# Sch.net
KiCad netlist of a schematic drawn in Altium Designer
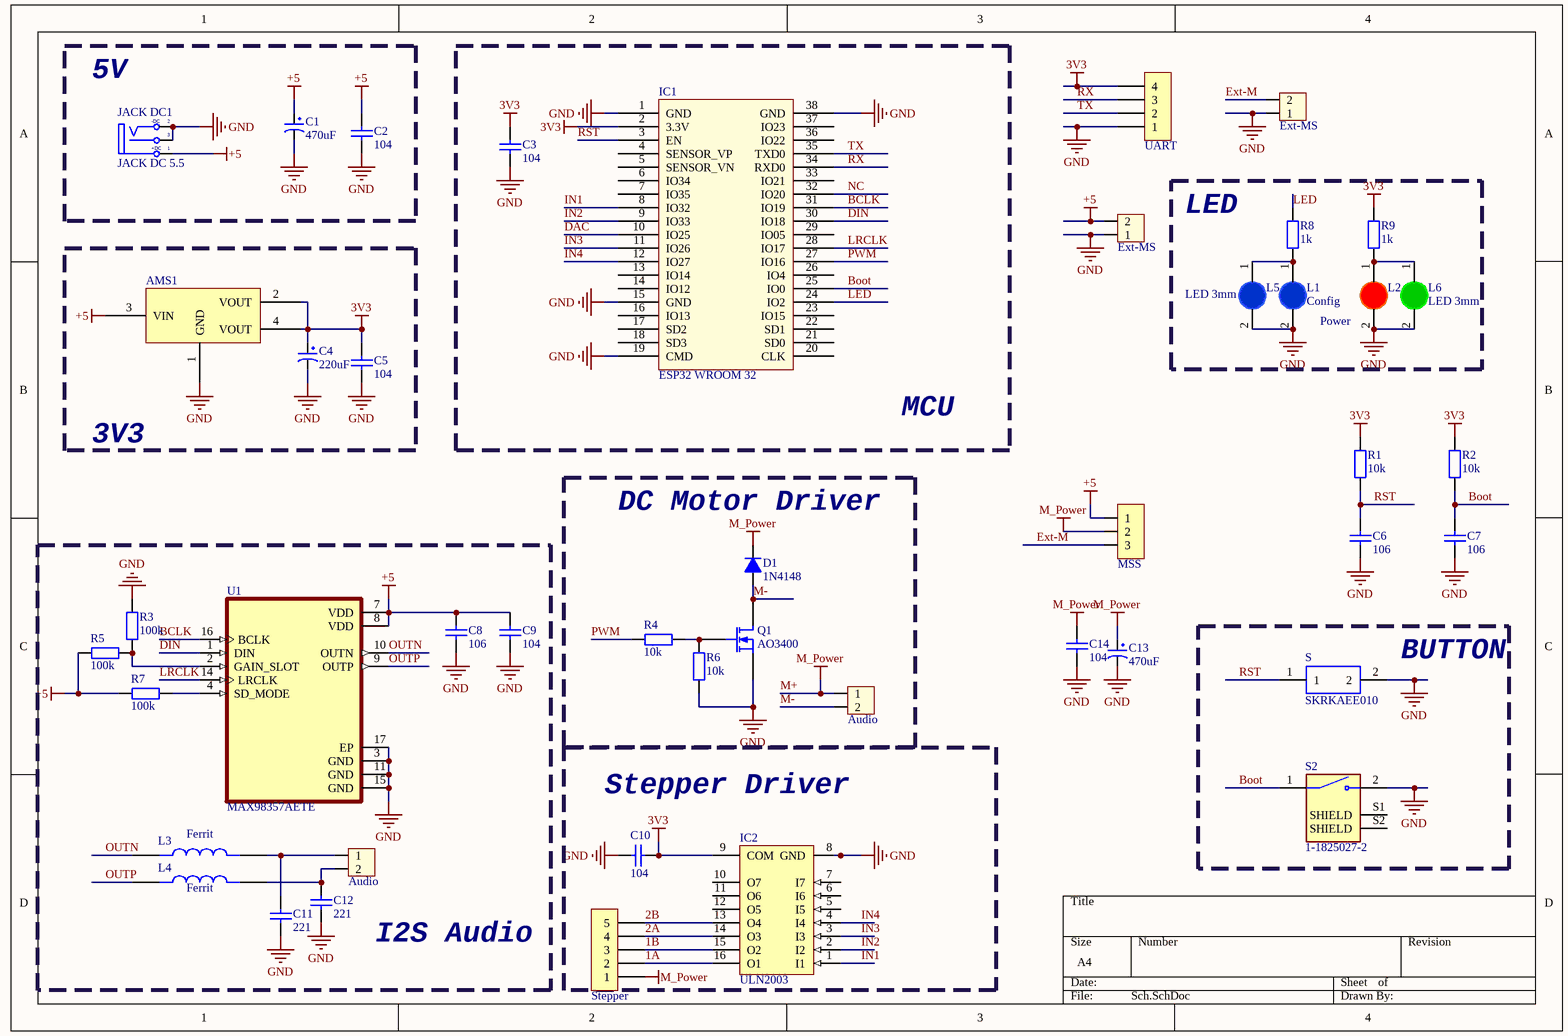
[diagram p0: Sch.SchDoc]

(export (version "E")
  (design (tool "Eeschema 10.0.6"))
  (components
    (comp (ref "AMS1")
      (value "~")
      (footprint "SOT223")
      (description "Dán")
      (libsource (lib "MinhPC_Library") (part "AMS1117 SMD"))
    )
    (comp (ref "C1")
      (value "470uF")
      (footprint "tu hoa 8mm")
      (description "Cắm")
      (libsource (lib "MinhPC_Library") (part "Tu Hoa 470uF 16V 8x11"))
    )
    (comp (ref "C2")
      (value "104")
      (footprint "tu 0805")
      (description "Dán")
      (libsource (lib "MinhPC_Library") (part "Tu 0805 104 50V 10%"))
    )
    (comp (ref "C3")
      (value "104")
      (footprint "tu 0805")
      (description "Dán")
      (libsource (lib "MinhPC_Library") (part "Tu 0805 104 50V 10%"))
    )
    (comp (ref "C4")
      (value "220uF")
      (footprint "tu hoa 5mm")
      (description "Cắm")
      (libsource (lib "MinhPC_Library") (part "Tu Hoa 220uF 10V 6x11"))
    )
    (comp (ref "C5")
      (value "104")
      (footprint "tu 0805")
      (description "Dán")
      (libsource (lib "MinhPC_Library") (part "Tu 0805 104 50V 10%"))
    )
    (comp (ref "C6")
      (value "106")
      (footprint "tu 0805")
      (description "Dán")
      (libsource (lib "MinhPC_Library") (part "Tu 0805 106 16V 10%"))
    )
    (comp (ref "C7")
      (value "106")
      (footprint "tu 0805")
      (description "Dán")
      (libsource (lib "MinhPC_Library") (part "Tu 0805 106 16V 10%"))
    )
    (comp (ref "C8")
      (value "106")
      (footprint "tu 0805")
      (description "Dán")
      (libsource (lib "MinhPC_Library") (part "Tu 0805 106 16V 10%"))
    )
    (comp (ref "C9")
      (value "104")
      (footprint "tu 0805")
      (description "Dán")
      (libsource (lib "MinhPC_Library") (part "Tu 0805 104 50V 10%"))
    )
    (comp (ref "C10")
      (value "104")
      (footprint "tu 0805")
      (description "Dán")
      (libsource (lib "MinhPC_Library") (part "Tu 0805 104 50V 10%"))
    )
    (comp (ref "C11")
      (value "221")
      (footprint "tu 0805")
      (description "Dán")
      (libsource (lib "MinhPC_Library") (part "Tu 0805 224 50V 10%"))
    )
    (comp (ref "C12")
      (value "221")
      (footprint "tu 0805")
      (description "Dán")
      (libsource (lib "MinhPC_Library") (part "Tu 0805 224 50V 10%"))
    )
    (comp (ref "C13")
      (value "470uF")
      (footprint "tu hoa 8mm")
      (description "Cắm")
      (libsource (lib "MinhPC_Library") (part "Tu Hoa 470uF 16V 8x11"))
    )
    (comp (ref "C14")
      (value "104")
      (footprint "tu 0805")
      (description "Dán")
      (libsource (lib "MinhPC_Library") (part "Tu 0805 104 50V 10%"))
    )
    (comp (ref "D1")
      (value "1N4148")
      (footprint "DIODE SOD323F")
      (description "SMD")
      (libsource (lib "MinhPC_Library") (part "1N4148"))
    )
    (comp (ref "H1")
      (value "UART")
      (footprint "XH2.54M-4")
      (description "Cắm")
      (libsource (lib "MinhPC_Library") (part "Header 4P 2.54 Duc Thang"))
    )
    (comp (ref "H2")
      (value "Audio")
      (footprint "XH2.54M-2")
      (description "Cắm")
      (libsource (lib "MinhPC_Library") (part "Header 2P 2.54 Duc Thang"))
    )
    (comp (ref "H3")
      (value "Audio")
      (footprint "XH2.54M-2")
      (description "Cắm")
      (libsource (lib "MinhPC_Library") (part "Header 2P 2.54 Duc Thang"))
    )
    (comp (ref "H4")
      (value "Stepper")
      (footprint "XH2.54M-5")
      (description "Cắm")
      (libsource (lib "MinhPC_Library") (part "Header 5P 2.54 Duc Thang"))
    )
    (comp (ref "H5")
      (value "Ext-MS")
      (footprint "XH2.54M-2")
      (description "Cắm")
      (libsource (lib "") (part "Header 2P 2.54 Duc Thang_1"))
    )
    (comp (ref "H6")
      (value "Ext-MS")
      (footprint "XH2.54M-2")
      (description "Cắm")
      (libsource (lib "") (part "Header 2P 2.54 Duc Thang_1"))
    )
    (comp (ref "IC1")
      (value "ESP32 WROOM 32")
      (footprint "ESP32-WROOM-32D")
      (libsource (lib "MinhPC_Library") (part "ESP32 WROOM 32"))
    )
    (comp (ref "IC2")
      (value "ULN2003")
      (footprint "SOP 16")
      (description "Dán")
      (libsource (lib "MinhPC_Library") (part "ULN2003A SMD"))
    )
    (comp (ref "JACK DC1")
      (value "JACK DC 5.5")
      (footprint "JACK DC 5.5")
      (libsource (lib "MinhPC_Library") (part "JACK DC 5.5"))
    )
    (comp (ref "JP1")
      (value "MSS")
      (footprint "JP 1x3 DT")
      (description "Cắm")
      (libsource (lib "MinhPC_Library") (part "JP 1x3 2.54 Duc Thang"))
    )
    (comp (ref "L1")
      (value "Config")
      (footprint "LED-0805-Blue")
      (description "Dán")
      (libsource (lib "MinhPC_Library") (part "LED 0805 Xanh Duong"))
    )
    (comp (ref "L2")
      (value "Power")
      (footprint "LED-0805-Red")
      (description "Dán")
      (libsource (lib "MinhPC_Library") (part "LED 0805 Do"))
    )
    (comp (ref "L3")
      (value "Ferrit")
      (footprint "INDC2012X105N")
      (description "IND 1uH 0.05A 400mâ„¦")
      (fields (field (name "MP") "AIML-0805-1R0K-T") (field (name "MF") "Abracon"))
      (libsource (lib "AIML-0805-1R0K-T") (part "AIML-0805-1R0K-T"))
    )
    (comp (ref "L4")
      (value "Ferrit")
      (footprint "INDC2012X105N")
      (description "IND 1uH 0.05A 400mâ„¦")
      (fields (field (name "MP") "AIML-0805-1R0K-T") (field (name "MF") "Abracon"))
      (libsource (lib "AIML-0805-1R0K-T") (part "AIML-0805-1R0K-T"))
    )
    (comp (ref "L5")
      (value "LED 3mm")
      (footprint "LED-3MM-BLUE")
      (description "Cắm")
      (libsource (lib "MinhPC_Library") (part "LED 3mm Xanh Duong"))
    )
    (comp (ref "L6")
      (value "LED 3mm")
      (footprint "LED-3MM-GREEN")
      (description "Cắm")
      (libsource (lib "MinhPC_Library") (part "LED 3mm Xanh La"))
    )
    (comp (ref "Q1")
      (value "AO3400")
      (footprint "SOT23")
      (description "N-Channel MOSFET")
      (fields (field (name "PUBLISHER") "Altium Limited"))
      (libsource (lib "MinhPC_Library") (part "Si2302DS"))
    )
    (comp (ref "R1")
      (value "10k")
      (footprint "tro smd 0805")
      (description "Dán")
      (libsource (lib "MinhPC_Library") (part "Tro 0805 5% 10k"))
    )
    (comp (ref "R2")
      (value "10k")
      (footprint "tro smd 0805")
      (description "Dán")
      (libsource (lib "MinhPC_Library") (part "Tro 0805 5% 10k"))
    )
    (comp (ref "R3")
      (value "100k")
      (footprint "tro smd 0805")
      (description "Dán")
      (libsource (lib "MinhPC_Library") (part "Tro 0805 5% 10k"))
    )
    (comp (ref "R4")
      (value "10k")
      (footprint "tro smd 0805")
      (description "Dán")
      (libsource (lib "MinhPC_Library") (part "Tro 0805 5% 10k"))
    )
    (comp (ref "R5")
      (value "100k")
      (footprint "tro smd 0805")
      (description "Dán")
      (libsource (lib "MinhPC_Library") (part "Tro 0805 5% 10k"))
    )
    (comp (ref "R6")
      (value "10k")
      (footprint "tro smd 0805")
      (description "Dán")
      (libsource (lib "MinhPC_Library") (part "Tro 0805 5% 10k"))
    )
    (comp (ref "R7")
      (value "100k")
      (footprint "tro smd 0805")
      (description "Dán")
      (libsource (lib "MinhPC_Library") (part "Tro 0805 5% 10k"))
    )
    (comp (ref "R8")
      (value "1k")
      (footprint "tro smd 0805")
      (description "Dán")
      (libsource (lib "MinhPC_Library") (part "Tro 0805 5% 10k"))
    )
    (comp (ref "R9")
      (value "1k")
      (footprint "tro smd 0805")
      (description "Dán")
      (libsource (lib "MinhPC_Library") (part "Tro 0805 5% 10k"))
    )
    (comp (ref "S")
      (value "SKRKAEE010")
      (footprint "SKRK")
      (description "Switch Tactile N.O. SPST Round Button Gull Wing 0.05A 12VDC 1.57N SMD T/R")
      (fields (field (name "MF") "ALPS"))
      (libsource (lib "SKRKAEE010") (part "SKRKAEE010"))
    )
    (comp (ref "S2")
      (value "1-1825027-2")
      (footprint "SW_1-1825027-2")
      (description "Tactile Switch SPST-NO Side Actuated Through Hole, Right Angle")
      (fields (field (name "MF") "TE Connectivity"))
      (libsource (lib "1-1825027-2") (part "1-1825027-2"))
    )
    (comp (ref "U1")
      (value "MAX98357AETE")
      (footprint "QFN50P300X300X80-17N")
      (description "Audio Amp Speaker 1-CH Mono 3.2W Class-D 16-Pin TQFN EP T/R")
      (fields (field (name "MF") "Maxim Integrated"))
      (libsource (lib "MAX98357AETE") (part "MAX98357AETE"))
    )
  )
  (nets
    (net (code "1") (name "+5") (class "Default")
      (node (ref "AMS1") (pin "3") (pinfunction "VIN_3") (pintype "passive"))
      (node (ref "C1") (pin "1") (pinfunction "1_1") (pintype "passive"))
      (node (ref "C2") (pin "1") (pinfunction "1_1") (pintype "passive"))
      (node (ref "C8") (pin "1") (pinfunction "1_1") (pintype "passive"))
      (node (ref "C9") (pin "1") (pinfunction "1_1") (pintype "passive"))
      (node (ref "H6") (pin "2") (pinfunction "2_2") (pintype "passive"))
      (node (ref "JACK DC1") (pin "1") (pinfunction "T_1") (pintype "passive"))
      (node (ref "JP1") (pin "1") (pinfunction "1_1") (pintype "passive"))
      (node (ref "R5") (pin "2") (pinfunction "2_2") (pintype "passive"))
      (node (ref "R7") (pin "2") (pinfunction "2_2") (pintype "passive"))
      (node (ref "U1") (pin "7") (pinfunction "VDD_7") (pintype "power_in"))
      (node (ref "U1") (pin "8") (pinfunction "VDD_8") (pintype "power_in"))
    )
    (net (code "2") (name "/1A") (class "Default")
      (node (ref "H4") (pin "2") (pinfunction "2_2") (pintype "passive"))
      (node (ref "IC2") (pin "16") (pinfunction "O1_16") (pintype "open_collector"))
    )
    (net (code "3") (name "/1B") (class "Default")
      (node (ref "H4") (pin "3") (pinfunction "3_3") (pintype "passive"))
      (node (ref "IC2") (pin "15") (pinfunction "O2_15") (pintype "open_collector"))
    )
    (net (code "4") (name "/2A") (class "Default")
      (node (ref "H4") (pin "4") (pinfunction "4_4") (pintype "passive"))
      (node (ref "IC2") (pin "14") (pinfunction "O3_14") (pintype "open_collector"))
    )
    (net (code "5") (name "/2B") (class "Default")
      (node (ref "H4") (pin "5") (pinfunction "5_5") (pintype "passive"))
      (node (ref "IC2") (pin "13") (pinfunction "O4_13") (pintype "open_collector"))
    )
    (net (code "6") (name "/BCLK") (class "Default")
      (node (ref "IC1") (pin "31") (pinfunction "IO19_31") (pintype "passive"))
      (node (ref "U1") (pin "16") (pinfunction "BCLK_16") (pintype "input"))
    )
    (net (code "7") (name "/Boot") (class "Default")
      (node (ref "C7") (pin "1") (pinfunction "1_1") (pintype "passive"))
      (node (ref "IC1") (pin "25") (pinfunction "IO0_25") (pintype "passive"))
      (node (ref "R2") (pin "1") (pinfunction "1_1") (pintype "passive"))
      (node (ref "S2") (pin "1") (pinfunction "1_1") (pintype "passive"))
    )
    (net (code "8") (name "/DAC") (class "Default")
      (node (ref "IC1") (pin "10") (pinfunction "IO25_10") (pintype "passive"))
    )
    (net (code "9") (name "/DIN") (class "Default")
      (node (ref "IC1") (pin "30") (pinfunction "IO18_30") (pintype "passive"))
      (node (ref "U1") (pin "1") (pinfunction "DIN_1") (pintype "input"))
    )
    (net (code "10") (name "/Ext-M") (class "Default")
      (node (ref "H5") (pin "2") (pinfunction "2_2") (pintype "passive"))
      (node (ref "JP1") (pin "3") (pinfunction "3_3") (pintype "passive"))
    )
    (net (code "11") (name "/IN1") (class "Default")
      (node (ref "IC1") (pin "8") (pinfunction "IO32_8") (pintype "passive"))
      (node (ref "IC2") (pin "1") (pinfunction "I1_1") (pintype "input"))
    )
    (net (code "12") (name "/IN2") (class "Default")
      (node (ref "IC1") (pin "9") (pinfunction "IO33_9") (pintype "passive"))
      (node (ref "IC2") (pin "2") (pinfunction "I2_2") (pintype "input"))
    )
    (net (code "13") (name "/IN3") (class "Default")
      (node (ref "IC1") (pin "11") (pinfunction "IO26_11") (pintype "passive"))
      (node (ref "IC2") (pin "3") (pinfunction "I3_3") (pintype "input"))
    )
    (net (code "14") (name "/IN4") (class "Default")
      (node (ref "IC1") (pin "12") (pinfunction "IO27_12") (pintype "passive"))
      (node (ref "IC2") (pin "4") (pinfunction "I4_4") (pintype "input"))
    )
    (net (code "15") (name "/LED") (class "Default")
      (node (ref "IC1") (pin "24") (pinfunction "IO2_24") (pintype "passive"))
      (node (ref "R8") (pin "2") (pinfunction "2_2") (pintype "passive"))
    )
    (net (code "16") (name "/LRCLK") (class "Default")
      (node (ref "IC1") (pin "28") (pinfunction "IO17_28") (pintype "passive"))
      (node (ref "U1") (pin "14") (pinfunction "LRCLK_14") (pintype "input"))
    )
    (net (code "17") (name "/M-") (class "Default")
      (node (ref "D1") (pin "1") (pinfunction "A_1") (pintype "passive"))
      (node (ref "H2") (pin "2") (pinfunction "2_2") (pintype "passive"))
      (node (ref "Q1") (pin "3") (pinfunction "D_3") (pintype "passive"))
    )
    (net (code "18") (name "/NC") (class "Default")
      (node (ref "IC1") (pin "32") (pinfunction "IO20_32") (pintype "passive"))
    )
    (net (code "19") (name "/OUTN") (class "Default")
      (node (ref "L3") (pin "1") (pinfunction "1_1") (pintype "passive"))
      (node (ref "U1") (pin "10") (pinfunction "OUTN_10") (pintype "output"))
    )
    (net (code "20") (name "/OUTP") (class "Default")
      (node (ref "L4") (pin "1") (pinfunction "1_1") (pintype "passive"))
      (node (ref "U1") (pin "9") (pinfunction "OUTP_9") (pintype "output"))
    )
    (net (code "21") (name "/PWM") (class "Default")
      (node (ref "IC1") (pin "27") (pinfunction "IO16_27") (pintype "passive"))
      (node (ref "R4") (pin "2") (pinfunction "2_2") (pintype "passive"))
    )
    (net (code "22") (name "/RST") (class "Default")
      (node (ref "C6") (pin "1") (pinfunction "1_1") (pintype "passive"))
      (node (ref "IC1") (pin "3") (pinfunction "EN_3") (pintype "passive"))
      (node (ref "R1") (pin "1") (pinfunction "1_1") (pintype "passive"))
      (node (ref "S") (pin "1") (pinfunction "1_1") (pintype "passive"))
    )
    (net (code "23") (name "/RX") (class "Default")
      (node (ref "H1") (pin "3") (pinfunction "3_3") (pintype "passive"))
      (node (ref "IC1") (pin "34") (pinfunction "RXD0_34") (pintype "passive"))
    )
    (net (code "24") (name "/TX") (class "Default")
      (node (ref "H1") (pin "2") (pinfunction "2_2") (pintype "passive"))
      (node (ref "IC1") (pin "35") (pinfunction "TXD0_35") (pintype "passive"))
    )
    (net (code "25") (name "3V3") (class "Default")
      (node (ref "AMS1") (pin "2") (pinfunction "VOUT_2") (pintype "passive"))
      (node (ref "AMS1") (pin "4") (pinfunction "VOUT_4") (pintype "passive"))
      (node (ref "C10") (pin "1") (pinfunction "1_1") (pintype "passive"))
      (node (ref "C3") (pin "1") (pinfunction "1_1") (pintype "passive"))
      (node (ref "C4") (pin "1") (pinfunction "1_1") (pintype "passive"))
      (node (ref "C5") (pin "1") (pinfunction "1_1") (pintype "passive"))
      (node (ref "H1") (pin "4") (pinfunction "4_4") (pintype "passive"))
      (node (ref "IC1") (pin "2") (pinfunction "3.3V_2") (pintype "passive"))
      (node (ref "IC2") (pin "9") (pinfunction "COM_9") (pintype "passive"))
      (node (ref "R1") (pin "2") (pinfunction "2_2") (pintype "passive"))
      (node (ref "R2") (pin "2") (pinfunction "2_2") (pintype "passive"))
      (node (ref "R9") (pin "2") (pinfunction "2_2") (pintype "passive"))
    )
    (net (code "26") (name "GND") (class "Default")
      (node (ref "AMS1") (pin "1") (pinfunction "GND_1") (pintype "passive"))
      (node (ref "C1") (pin "2") (pinfunction "2_2") (pintype "passive"))
      (node (ref "C10") (pin "2") (pinfunction "2_2") (pintype "passive"))
      (node (ref "C11") (pin "2") (pinfunction "2_2") (pintype "passive"))
      (node (ref "C12") (pin "2") (pinfunction "2_2") (pintype "passive"))
      (node (ref "C13") (pin "2") (pinfunction "2_2") (pintype "passive"))
      (node (ref "C14") (pin "2") (pinfunction "2_2") (pintype "passive"))
      (node (ref "C2") (pin "2") (pinfunction "2_2") (pintype "passive"))
      (node (ref "C3") (pin "2") (pinfunction "2_2") (pintype "passive"))
      (node (ref "C4") (pin "2") (pinfunction "2_2") (pintype "passive"))
      (node (ref "C5") (pin "2") (pinfunction "2_2") (pintype "passive"))
      (node (ref "C6") (pin "2") (pinfunction "2_2") (pintype "passive"))
      (node (ref "C7") (pin "2") (pinfunction "2_2") (pintype "passive"))
      (node (ref "C8") (pin "2") (pinfunction "2_2") (pintype "passive"))
      (node (ref "C9") (pin "2") (pinfunction "2_2") (pintype "passive"))
      (node (ref "H1") (pin "1") (pinfunction "1_1") (pintype "passive"))
      (node (ref "H5") (pin "1") (pinfunction "1_1") (pintype "passive"))
      (node (ref "H6") (pin "1") (pinfunction "1_1") (pintype "passive"))
      (node (ref "IC1") (pin "1") (pinfunction "GND_1") (pintype "passive"))
      (node (ref "IC1") (pin "15") (pinfunction "GND_15") (pintype "passive"))
      (node (ref "IC1") (pin "19") (pinfunction "CMD_19") (pintype "passive"))
      (node (ref "IC1") (pin "38") (pinfunction "GND_38") (pintype "passive"))
      (node (ref "IC2") (pin "8") (pinfunction "GND_8") (pintype "power_in"))
      (node (ref "JACK DC1") (pin "2") (pinfunction "TN_2") (pintype "passive"))
      (node (ref "JACK DC1") (pin "3") (pinfunction "S_3") (pintype "power_in"))
      (node (ref "L1") (pin "2") (pinfunction "K_2") (pintype "passive"))
      (node (ref "L2") (pin "2") (pinfunction "K_2") (pintype "passive"))
      (node (ref "L5") (pin "2") (pinfunction "K_2") (pintype "passive"))
      (node (ref "L6") (pin "2") (pinfunction "K_2") (pintype "passive"))
      (node (ref "Q1") (pin "2") (pinfunction "S_2") (pintype "passive"))
      (node (ref "R3") (pin "2") (pinfunction "2_2") (pintype "passive"))
      (node (ref "R6") (pin "2") (pinfunction "2_2") (pintype "passive"))
      (node (ref "S") (pin "2") (pinfunction "2_2") (pintype "passive"))
      (node (ref "S2") (pin "2") (pinfunction "2_2") (pintype "passive"))
      (node (ref "U1") (pin "11") (pinfunction "GND_11") (pintype "power_in"))
      (node (ref "U1") (pin "15") (pinfunction "GND_15") (pintype "power_in"))
      (node (ref "U1") (pin "17") (pinfunction "EP_17") (pintype "power_in"))
      (node (ref "U1") (pin "3") (pinfunction "GND_3") (pintype "power_in"))
    )
    (net (code "27") (name "M_Power") (class "Default")
      (node (ref "C13") (pin "1") (pinfunction "1_1") (pintype "passive"))
      (node (ref "C14") (pin "1") (pinfunction "1_1") (pintype "passive"))
      (node (ref "D1") (pin "2") (pinfunction "K_2") (pintype "passive"))
      (node (ref "H2") (pin "1") (pinfunction "1_1") (pintype "passive"))
      (node (ref "H4") (pin "1") (pinfunction "1_1") (pintype "passive"))
      (node (ref "JP1") (pin "2") (pinfunction "2_2") (pintype "passive"))
    )
    (net (code "28") (name "Net-(C11-Pad1)") (class "Default")
      (node (ref "C11") (pin "1") (pinfunction "1_1") (pintype "passive"))
      (node (ref "H3") (pin "1") (pinfunction "1_1") (pintype "passive"))
      (node (ref "L3") (pin "2") (pinfunction "2_2") (pintype "passive"))
    )
    (net (code "29") (name "Net-(C12-Pad1)") (class "Default")
      (node (ref "C12") (pin "1") (pinfunction "1_1") (pintype "passive"))
      (node (ref "H3") (pin "2") (pinfunction "2_2") (pintype "passive"))
      (node (ref "L4") (pin "2") (pinfunction "2_2") (pintype "passive"))
    )
    (net (code "30") (name "Net-(L1-A)") (class "Default")
      (node (ref "L1") (pin "1") (pinfunction "A_1") (pintype "passive"))
      (node (ref "L5") (pin "1") (pinfunction "A_1") (pintype "passive"))
      (node (ref "R8") (pin "1") (pinfunction "1_1") (pintype "passive"))
    )
    (net (code "31") (name "Net-(L2-A)") (class "Default")
      (node (ref "L2") (pin "1") (pinfunction "A_1") (pintype "passive"))
      (node (ref "L6") (pin "1") (pinfunction "A_1") (pintype "passive"))
      (node (ref "R9") (pin "1") (pinfunction "1_1") (pintype "passive"))
    )
    (net (code "32") (name "Net-(Q1-G)") (class "Default")
      (node (ref "Q1") (pin "1") (pinfunction "G_1") (pintype "passive"))
      (node (ref "R4") (pin "1") (pinfunction "1_1") (pintype "passive"))
      (node (ref "R6") (pin "1") (pinfunction "1_1") (pintype "passive"))
    )
    (net (code "33") (name "Net-(U1-GAIN_SLOT)") (class "Default")
      (node (ref "R3") (pin "1") (pinfunction "1_1") (pintype "passive"))
      (node (ref "R5") (pin "1") (pinfunction "1_1") (pintype "passive"))
      (node (ref "U1") (pin "2") (pinfunction "GAIN_SLOT_2") (pintype "input"))
    )
    (net (code "34") (name "Net-(U1-SD_MODE)") (class "Default")
      (node (ref "R7") (pin "1") (pinfunction "1_1") (pintype "passive"))
      (node (ref "U1") (pin "4") (pinfunction "SD_MODE_4") (pintype "input"))
    )
    (net (code "35") (name "unconnected-(IC1-CLK-Pad20)") (class "Default")
      (node (ref "IC1") (pin "20") (pinfunction "CLK_20") (pintype "passive"))
    )
    (net (code "36") (name "unconnected-(IC1-IO4-Pad26)") (class "Default")
      (node (ref "IC1") (pin "26") (pinfunction "IO4_26") (pintype "passive"))
    )
    (net (code "37") (name "unconnected-(IC1-IO05-Pad29)") (class "Default")
      (node (ref "IC1") (pin "29") (pinfunction "IO05_29") (pintype "passive"))
    )
    (net (code "38") (name "unconnected-(IC1-IO12-Pad14)") (class "Default")
      (node (ref "IC1") (pin "14") (pinfunction "IO12_14") (pintype "passive"))
    )
    (net (code "39") (name "unconnected-(IC1-IO13-Pad16)") (class "Default")
      (node (ref "IC1") (pin "16") (pinfunction "IO13_16") (pintype "passive"))
    )
    (net (code "40") (name "unconnected-(IC1-IO14-Pad13)") (class "Default")
      (node (ref "IC1") (pin "13") (pinfunction "IO14_13") (pintype "passive"))
    )
    (net (code "41") (name "unconnected-(IC1-IO15-Pad23)") (class "Default")
      (node (ref "IC1") (pin "23") (pinfunction "IO15_23") (pintype "passive"))
    )
    (net (code "42") (name "unconnected-(IC1-IO21-Pad33)") (class "Default")
      (node (ref "IC1") (pin "33") (pinfunction "IO21_33") (pintype "passive"))
    )
    (net (code "43") (name "unconnected-(IC1-IO22-Pad36)") (class "Default")
      (node (ref "IC1") (pin "36") (pinfunction "IO22_36") (pintype "passive"))
    )
    (net (code "44") (name "unconnected-(IC1-IO23-Pad37)") (class "Default")
      (node (ref "IC1") (pin "37") (pinfunction "IO23_37") (pintype "passive"))
    )
    (net (code "45") (name "unconnected-(IC1-IO34-Pad6)") (class "Default")
      (node (ref "IC1") (pin "6") (pinfunction "IO34_6") (pintype "passive"))
    )
    (net (code "46") (name "unconnected-(IC1-IO35-Pad7)") (class "Default")
      (node (ref "IC1") (pin "7") (pinfunction "IO35_7") (pintype "passive"))
    )
    (net (code "47") (name "unconnected-(IC1-SD0-Pad21)") (class "Default")
      (node (ref "IC1") (pin "21") (pinfunction "SD0_21") (pintype "passive"))
    )
    (net (code "48") (name "unconnected-(IC1-SD1-Pad22)") (class "Default")
      (node (ref "IC1") (pin "22") (pinfunction "SD1_22") (pintype "passive"))
    )
    (net (code "49") (name "unconnected-(IC1-SD2-Pad17)") (class "Default")
      (node (ref "IC1") (pin "17") (pinfunction "SD2_17") (pintype "passive"))
    )
    (net (code "50") (name "unconnected-(IC1-SD3-Pad18)") (class "Default")
      (node (ref "IC1") (pin "18") (pinfunction "SD3_18") (pintype "passive"))
    )
    (net (code "51") (name "unconnected-(IC1-SENSOR_VN-Pad5)") (class "Default")
      (node (ref "IC1") (pin "5") (pinfunction "SENSOR_VN_5") (pintype "passive"))
    )
    (net (code "52") (name "unconnected-(IC1-SENSOR_VP-Pad4)") (class "Default")
      (node (ref "IC1") (pin "4") (pinfunction "SENSOR_VP_4") (pintype "passive"))
    )
    (net (code "53") (name "unconnected-(IC2-I5-Pad5)") (class "Default")
      (node (ref "IC2") (pin "5") (pinfunction "I5_5") (pintype "input"))
    )
    (net (code "54") (name "unconnected-(IC2-I6-Pad6)") (class "Default")
      (node (ref "IC2") (pin "6") (pinfunction "I6_6") (pintype "input"))
    )
    (net (code "55") (name "unconnected-(IC2-I7-Pad7)") (class "Default")
      (node (ref "IC2") (pin "7") (pinfunction "I7_7") (pintype "input"))
    )
    (net (code "56") (name "unconnected-(IC2-O5-Pad12)") (class "Default")
      (node (ref "IC2") (pin "12") (pinfunction "O5_12") (pintype "open_collector"))
    )
    (net (code "57") (name "unconnected-(IC2-O6-Pad11)") (class "Default")
      (node (ref "IC2") (pin "11") (pinfunction "O6_11") (pintype "open_collector"))
    )
    (net (code "58") (name "unconnected-(IC2-O7-Pad10)") (class "Default")
      (node (ref "IC2") (pin "10") (pinfunction "O7_10") (pintype "open_collector"))
    )
    (net (code "59") (name "unconnected-(S2-SHIELD-PadS1)") (class "Default")
      (node (ref "S2") (pin "S1") (pinfunction "SHIELD_S1") (pintype "passive"))
    )
    (net (code "60") (name "unconnected-(S2-SHIELD-PadS2)") (class "Default")
      (node (ref "S2") (pin "S2") (pinfunction "SHIELD_S2") (pintype "passive"))
    )
  )
)
